# micShield.net
KiCad netlist of a schematic drawn in EAGLE
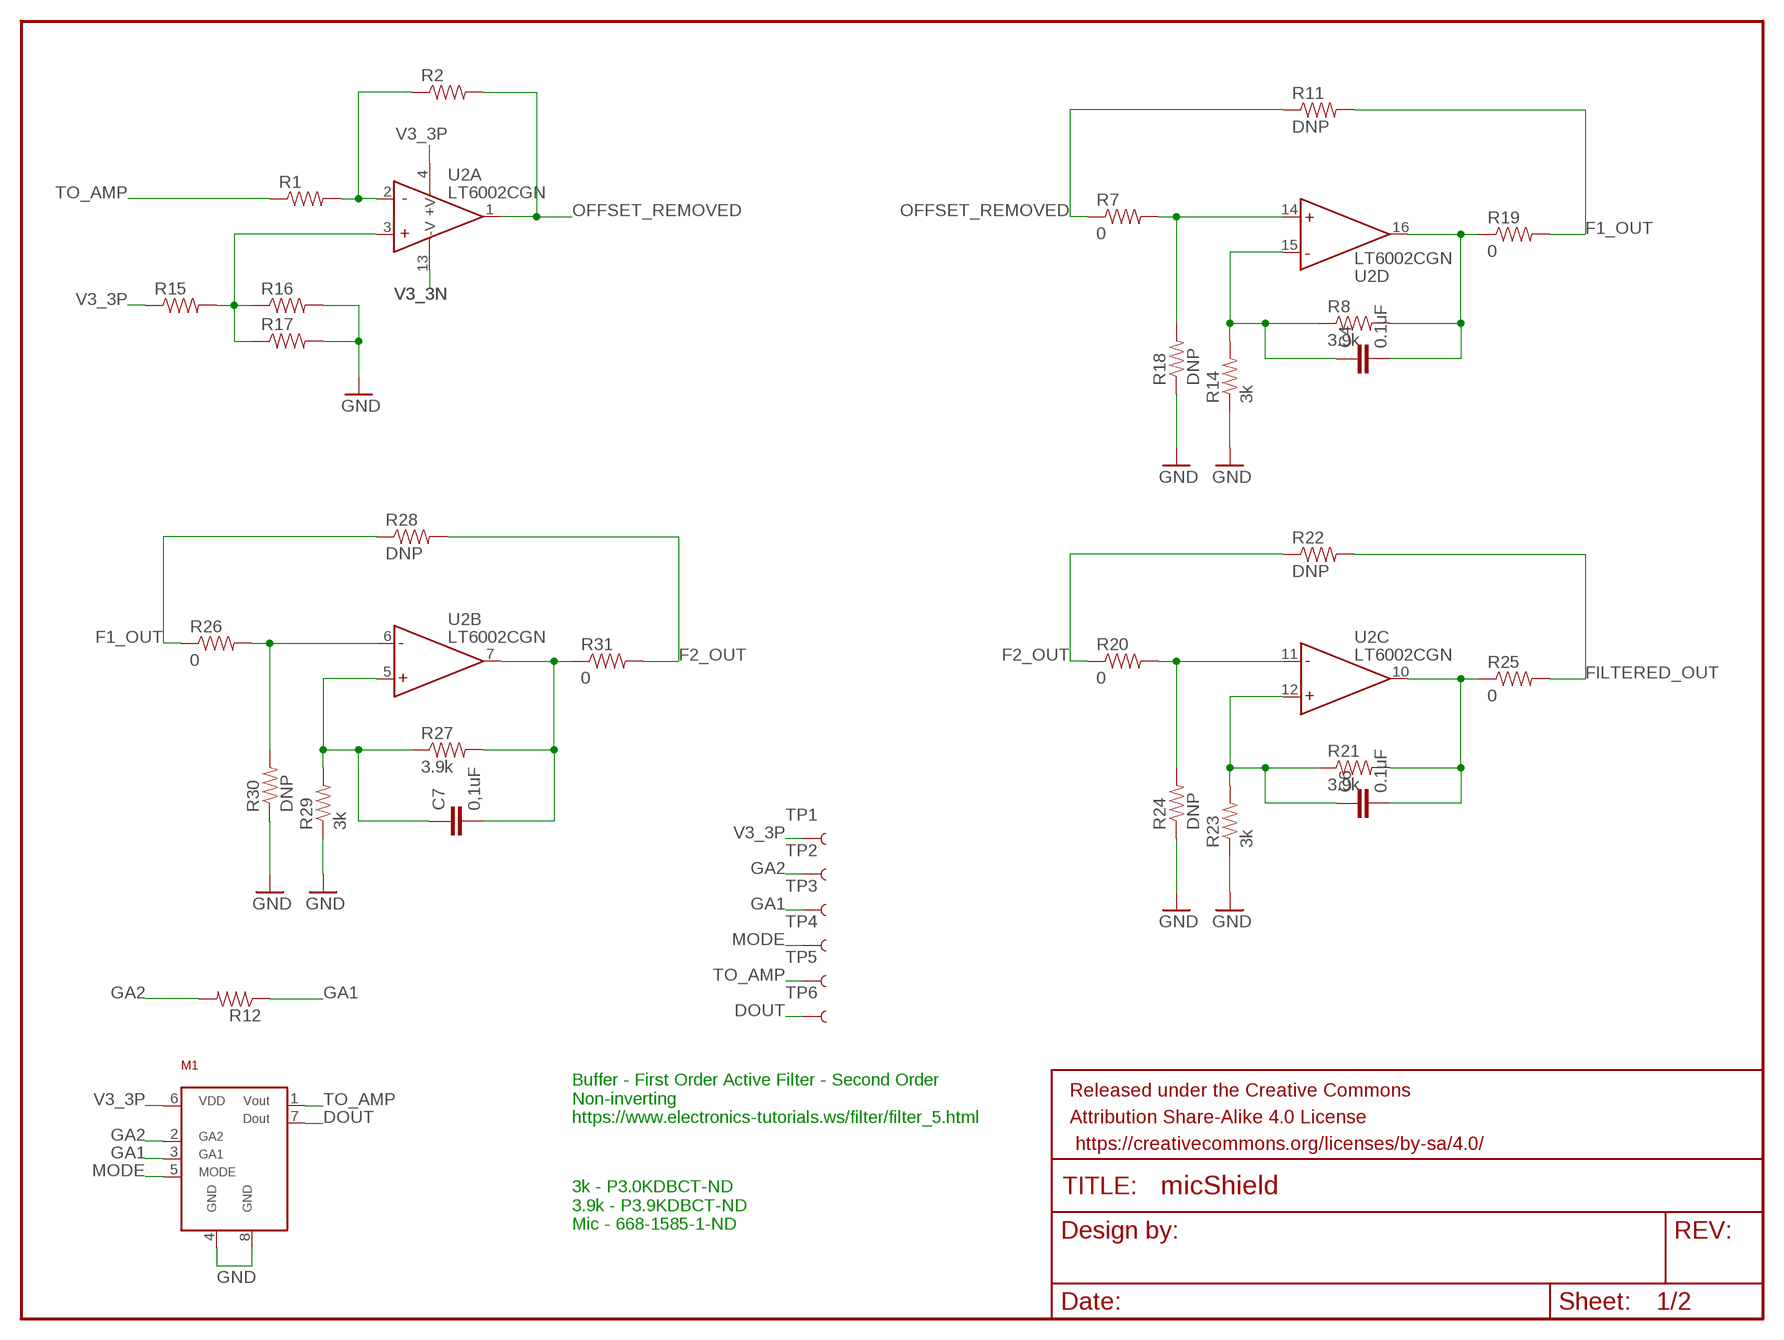
[diagram p0: schematic, sheet 1]
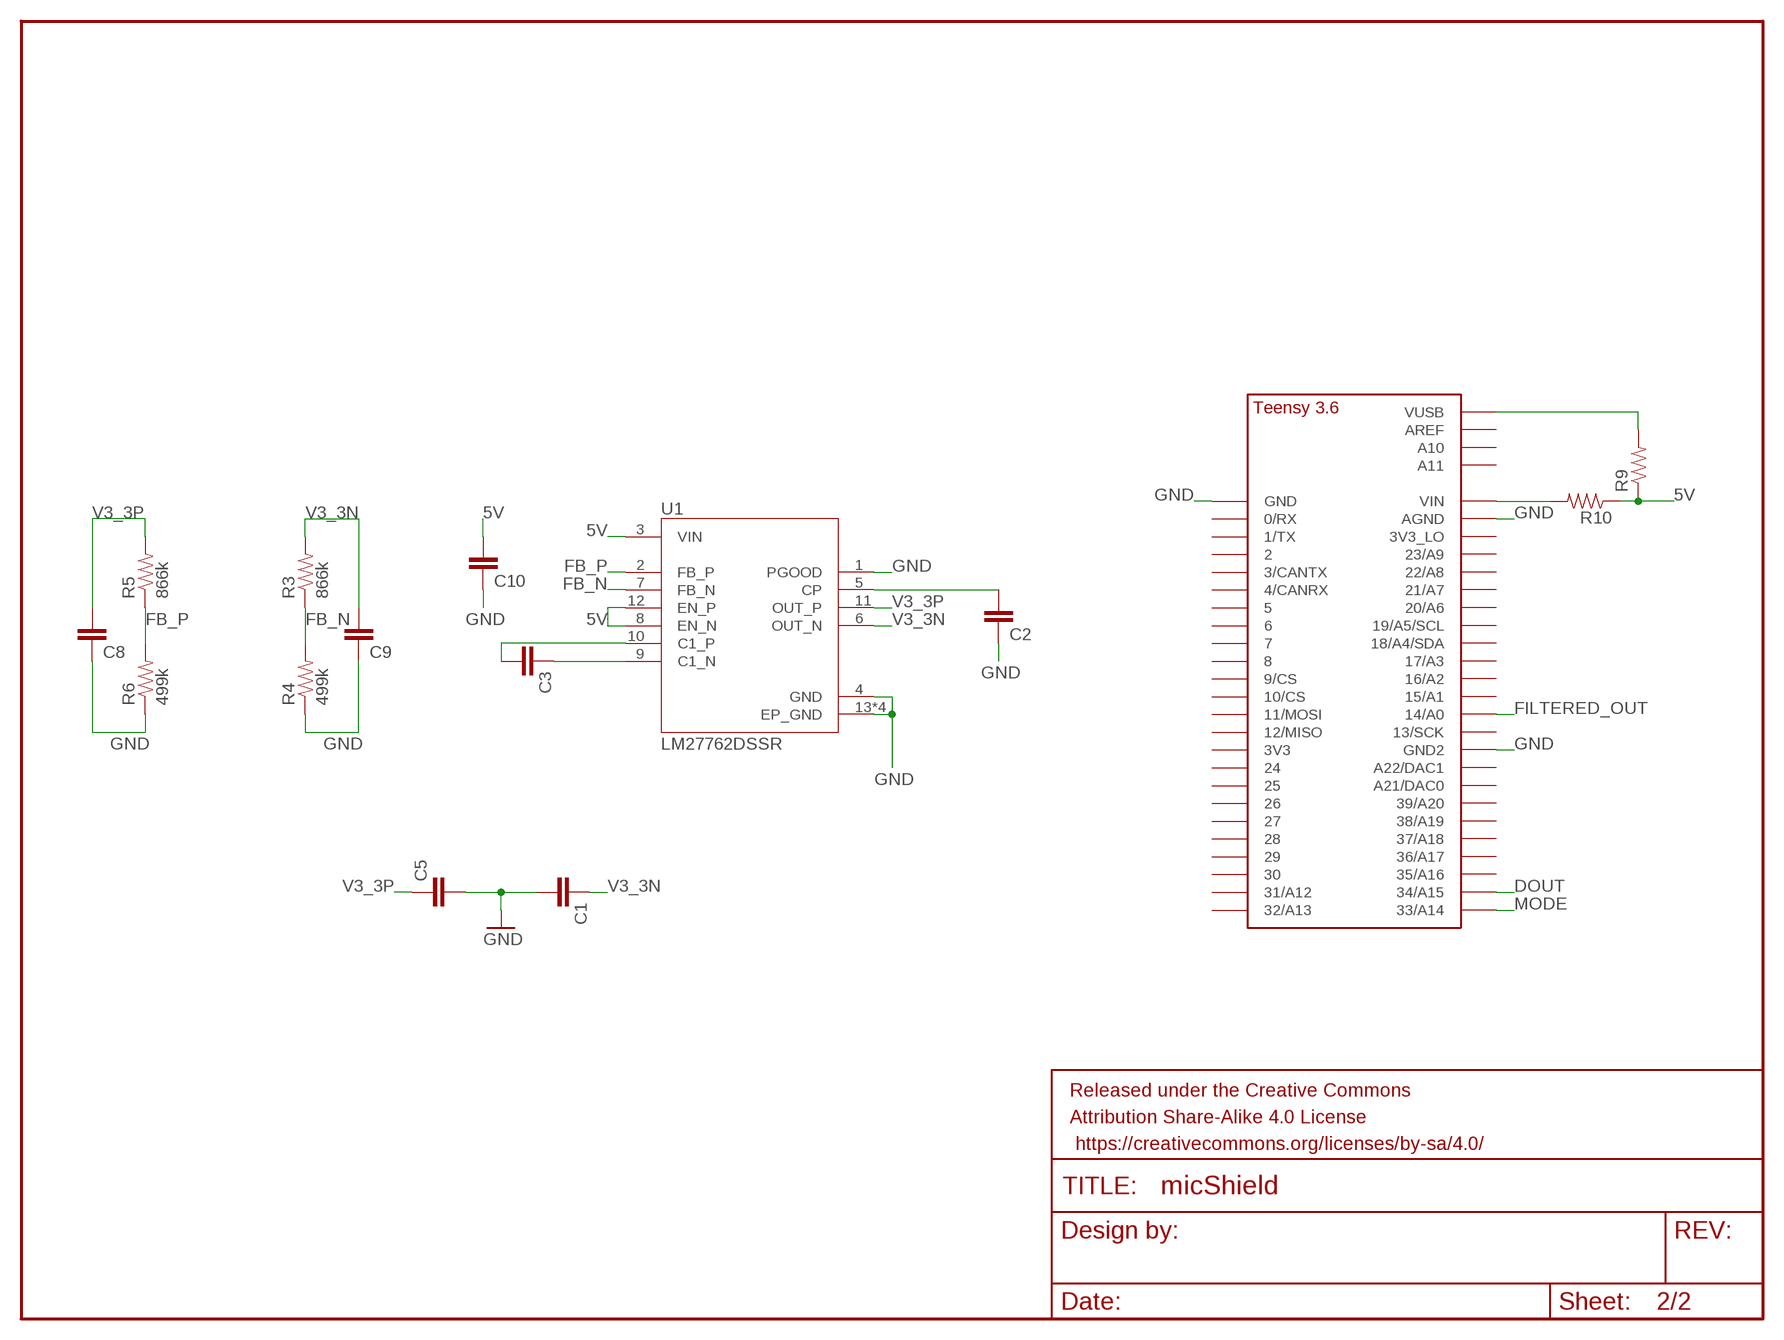
[diagram p1: schematic, sheet 2]

(export (version "E")
  (design (tool "Eeschema 10.0.6"))
  (components
    (comp (ref "C4")
      (value "0.1uF")
      (footprint "eagle-import:0402-CAP")
      (libsource (lib "eagle-import") (part "CAP0402-CAP"))
    )
    (comp (ref "C6")
      (value "0.1uF")
      (footprint "eagle-import:0402-CAP")
      (libsource (lib "eagle-import") (part "CAP0402-CAP"))
    )
    (comp (ref "C7")
      (value "0,1uF")
      (footprint "eagle-import:0402-CAP")
      (libsource (lib "eagle-import") (part "CAP0402-CAP"))
    )
    (comp (ref "FRAME1")
      (value "FRAME-LETTER")
      (footprint "eagle-import:CREATIVE_COMMONS")
      (libsource (lib "eagle-import") (part "FRAME-LETTER"))
    )
    (comp (ref "M1")
      (value "PMM-3738-VM1010-R")
      (footprint "eagle-import:PMM-3738-VM1010-R")
      (libsource (lib "eagle-import") (part "PMM-3738-VM1010-R"))
    )
    (comp (ref "R1")
      (value "RESISTOR0402")
      (footprint "eagle-import:0402-RES")
      (libsource (lib "eagle-import") (part "RESISTOR0402"))
    )
    (comp (ref "R2")
      (value "RESISTOR0402")
      (footprint "eagle-import:0402-RES")
      (libsource (lib "eagle-import") (part "RESISTOR0402"))
    )
    (comp (ref "R7")
      (value "0")
      (footprint "eagle-import:0402-RES")
      (libsource (lib "eagle-import") (part "RESISTOR0402"))
    )
    (comp (ref "R8")
      (value "3.9k")
      (footprint "eagle-import:0402-RES")
      (libsource (lib "eagle-import") (part "RESISTOR0402"))
    )
    (comp (ref "R11")
      (value "DNP")
      (footprint "eagle-import:0402-RES")
      (libsource (lib "eagle-import") (part "RESISTOR0402"))
    )
    (comp (ref "R12")
      (value "RESISTOR0402")
      (footprint "eagle-import:0402-RES")
      (libsource (lib "eagle-import") (part "RESISTOR0402"))
    )
    (comp (ref "R14")
      (value "3k")
      (footprint "eagle-import:0402-RES")
      (libsource (lib "eagle-import") (part "RESISTOR0402"))
    )
    (comp (ref "R15")
      (value "RESISTOR0402")
      (footprint "eagle-import:0402-RES")
      (libsource (lib "eagle-import") (part "RESISTOR0402"))
    )
    (comp (ref "R16")
      (value "RESISTOR0402")
      (footprint "eagle-import:0402-RES")
      (libsource (lib "eagle-import") (part "RESISTOR0402"))
    )
    (comp (ref "R17")
      (value "RESISTOR0402")
      (footprint "eagle-import:0402-RES")
      (libsource (lib "eagle-import") (part "RESISTOR0402"))
    )
    (comp (ref "R18")
      (value "DNP")
      (footprint "eagle-import:0402-RES")
      (libsource (lib "eagle-import") (part "RESISTOR0402"))
    )
    (comp (ref "R19")
      (value "0")
      (footprint "eagle-import:0402-RES")
      (libsource (lib "eagle-import") (part "RESISTOR0402"))
    )
    (comp (ref "R20")
      (value "0")
      (footprint "eagle-import:0402-RES")
      (libsource (lib "eagle-import") (part "RESISTOR0402"))
    )
    (comp (ref "R21")
      (value "3.9k")
      (footprint "eagle-import:0402-RES")
      (libsource (lib "eagle-import") (part "RESISTOR0402"))
    )
    (comp (ref "R22")
      (value "DNP")
      (footprint "eagle-import:0402-RES")
      (libsource (lib "eagle-import") (part "RESISTOR0402"))
    )
    (comp (ref "R23")
      (value "3k")
      (footprint "eagle-import:0402-RES")
      (libsource (lib "eagle-import") (part "RESISTOR0402"))
    )
    (comp (ref "R24")
      (value "DNP")
      (footprint "eagle-import:0402-RES")
      (libsource (lib "eagle-import") (part "RESISTOR0402"))
    )
    (comp (ref "R25")
      (value "0")
      (footprint "eagle-import:0402-RES")
      (libsource (lib "eagle-import") (part "RESISTOR0402"))
    )
    (comp (ref "R26")
      (value "0")
      (footprint "eagle-import:0402-RES")
      (libsource (lib "eagle-import") (part "RESISTOR0402"))
    )
    (comp (ref "R27")
      (value "3.9k")
      (footprint "eagle-import:0402-RES")
      (libsource (lib "eagle-import") (part "RESISTOR0402"))
    )
    (comp (ref "R28")
      (value "DNP")
      (footprint "eagle-import:0402-RES")
      (libsource (lib "eagle-import") (part "RESISTOR0402"))
    )
    (comp (ref "R29")
      (value "3k")
      (footprint "eagle-import:0402-RES")
      (libsource (lib "eagle-import") (part "RESISTOR0402"))
    )
    (comp (ref "R30")
      (value "DNP")
      (footprint "eagle-import:0402-RES")
      (libsource (lib "eagle-import") (part "RESISTOR0402"))
    )
    (comp (ref "R31")
      (value "0")
      (footprint "eagle-import:0402-RES")
      (libsource (lib "eagle-import") (part "RESISTOR0402"))
    )
    (comp (ref "TP1")
      (value "TEST-POINT3")
      (footprint "eagle-import:PAD.03X.03")
      (libsource (lib "eagle-import") (part "TEST-POINT3"))
    )
    (comp (ref "TP2")
      (value "TEST-POINT3")
      (footprint "eagle-import:PAD.03X.03")
      (libsource (lib "eagle-import") (part "TEST-POINT3"))
    )
    (comp (ref "TP3")
      (value "TEST-POINT3")
      (footprint "eagle-import:PAD.03X.03")
      (libsource (lib "eagle-import") (part "TEST-POINT3"))
    )
    (comp (ref "TP4")
      (value "TEST-POINT3")
      (footprint "eagle-import:PAD.03X.03")
      (libsource (lib "eagle-import") (part "TEST-POINT3"))
    )
    (comp (ref "TP5")
      (value "TEST-POINT3")
      (footprint "eagle-import:PAD.03X.03")
      (libsource (lib "eagle-import") (part "TEST-POINT3"))
    )
    (comp (ref "TP6")
      (value "TEST-POINT3")
      (footprint "eagle-import:PAD.03X.03")
      (libsource (lib "eagle-import") (part "TEST-POINT3"))
    )
    (comp (ref "U2")
      (value "LT6002CGN")
      (footprint "eagle-import:SSOP-16_GN")
      (fields (field (name "MANUFACTURER_PART_NUMBER") "LT6002CGN#PBF"))
      (libsource (lib "eagle-import") (part "LT6002CGN"))
    )
    (comp (ref "C1")
      (value "CAP0603-CAP")
      (footprint "eagle-import:0603-CAP")
      (libsource (lib "eagle-import") (part "CAP0603-CAP"))
    )
    (comp (ref "C2")
      (value "CAP0603-CAP")
      (footprint "eagle-import:0603-CAP")
      (libsource (lib "eagle-import") (part "CAP0603-CAP"))
    )
    (comp (ref "C3")
      (value "CAP0402-CAP")
      (footprint "eagle-import:0402-CAP")
      (libsource (lib "eagle-import") (part "CAP0402-CAP"))
    )
    (comp (ref "C5")
      (value "CAP0603-CAP")
      (footprint "eagle-import:0603-CAP")
      (libsource (lib "eagle-import") (part "CAP0603-CAP"))
    )
    (comp (ref "C8")
      (value "CAP0603-CAP")
      (footprint "eagle-import:0603-CAP")
      (libsource (lib "eagle-import") (part "CAP0603-CAP"))
    )
    (comp (ref "C9")
      (value "CAP0603-CAP")
      (footprint "eagle-import:0603-CAP")
      (libsource (lib "eagle-import") (part "CAP0603-CAP"))
    )
    (comp (ref "C10")
      (value "CAP0603-CAP")
      (footprint "eagle-import:0603-CAP")
      (libsource (lib "eagle-import") (part "CAP0603-CAP"))
    )
    (comp (ref "FRAME2")
      (value "FRAME-LETTER")
      (footprint "eagle-import:CREATIVE_COMMONS")
      (libsource (lib "eagle-import") (part "FRAME-LETTER"))
    )
    (comp (ref "R3")
      (value "866k")
      (footprint "eagle-import:0402-RES")
      (libsource (lib "eagle-import") (part "RESISTOR0402"))
    )
    (comp (ref "R4")
      (value "499k")
      (footprint "eagle-import:0402-RES")
      (libsource (lib "eagle-import") (part "RESISTOR0402"))
    )
    (comp (ref "R5")
      (value "866k")
      (footprint "eagle-import:0402-RES")
      (libsource (lib "eagle-import") (part "RESISTOR0402"))
    )
    (comp (ref "R6")
      (value "499k")
      (footprint "eagle-import:0402-RES")
      (libsource (lib "eagle-import") (part "RESISTOR0402"))
    )
    (comp (ref "R9")
      (value "RESISTOR0402")
      (footprint "eagle-import:0402-RES")
      (libsource (lib "eagle-import") (part "RESISTOR0402"))
    )
    (comp (ref "R10")
      (value "RESISTOR0402")
      (footprint "eagle-import:0402-RES")
      (libsource (lib "eagle-import") (part "RESISTOR0402"))
    )
    (comp (ref "U$1")
      (value "TEENSY_3.5/3.6_BASIC")
      (footprint "eagle-import:TEENSY_3.5_3.6_BASIC")
      (libsource (lib "eagle-import") (part "TEENSY_3.5/3.6_BASIC"))
    )
    (comp (ref "U1")
      (value "LM27762DSSR")
      (footprint "eagle-import:VREG_LM27762DSSR")
      (fields (field (name "MF") "Texas Instruments"))
      (libsource (lib "eagle-import") (part "LM27762DSSR"))
    )
  )
  (nets
    (net (code "1") (name "5V") (class "Default")
      (node (ref "C10") (pin "2") (pinfunction "2_2") (pintype "passive"))
      (node (ref "R10") (pin "1") (pinfunction "1_1") (pintype "passive"))
      (node (ref "R9") (pin "1") (pinfunction "1_1") (pintype "passive"))
      (node (ref "U1") (pin "12") (pinfunction "EN_P_12") (pintype "input"))
      (node (ref "U1") (pin "3") (pinfunction "VIN_3") (pintype "input"))
      (node (ref "U1") (pin "8") (pinfunction "EN_N_8") (pintype "input"))
    )
    (net (code "2") (name "DOUT") (class "Default")
      (node (ref "M1") (pin "7") (pinfunction "P$7_7") (pintype "bidirectional"))
      (node (ref "TP6") (pin "P$1") (pinfunction "1_P$1") (pintype "bidirectional"))
      (node (ref "U$1") (pin "34/A15") (pinfunction "34/A15_34/A15") (pintype "bidirectional"))
    )
    (net (code "3") (name "F1_OUT") (class "Default")
      (node (ref "R11") (pin "2") (pinfunction "2_2") (pintype "passive"))
      (node (ref "R19") (pin "2") (pinfunction "2_2") (pintype "passive"))
      (node (ref "R26") (pin "1") (pinfunction "1_1") (pintype "passive"))
      (node (ref "R28") (pin "1") (pinfunction "1_1") (pintype "passive"))
    )
    (net (code "4") (name "F2_OUT") (class "Default")
      (node (ref "R20") (pin "1") (pinfunction "1_1") (pintype "passive"))
      (node (ref "R22") (pin "1") (pinfunction "1_1") (pintype "passive"))
      (node (ref "R28") (pin "2") (pinfunction "2_2") (pintype "passive"))
      (node (ref "R31") (pin "2") (pinfunction "2_2") (pintype "passive"))
    )
    (net (code "5") (name "FB_N") (class "Default")
      (node (ref "R3") (pin "1") (pinfunction "1_1") (pintype "passive"))
      (node (ref "R4") (pin "2") (pinfunction "2_2") (pintype "passive"))
      (node (ref "U1") (pin "7") (pinfunction "FB_N_7") (pintype "input"))
    )
    (net (code "6") (name "FB_P") (class "Default")
      (node (ref "R5") (pin "1") (pinfunction "1_1") (pintype "passive"))
      (node (ref "R6") (pin "2") (pinfunction "2_2") (pintype "passive"))
      (node (ref "U1") (pin "2") (pinfunction "FB_P_2") (pintype "input"))
    )
    (net (code "7") (name "FILTERED_OUT") (class "Default")
      (node (ref "R22") (pin "2") (pinfunction "2_2") (pintype "passive"))
      (node (ref "R25") (pin "2") (pinfunction "2_2") (pintype "passive"))
      (node (ref "U$1") (pin "14/A0") (pinfunction "14/A0_14/A0") (pintype "bidirectional"))
    )
    (net (code "8") (name "GA1") (class "Default")
      (node (ref "M1") (pin "3") (pinfunction "P$3_3") (pintype "bidirectional"))
      (node (ref "R12") (pin "1") (pinfunction "1_1") (pintype "passive"))
      (node (ref "TP3") (pin "P$1") (pinfunction "1_P$1") (pintype "bidirectional"))
    )
    (net (code "9") (name "GA2") (class "Default")
      (node (ref "M1") (pin "2") (pinfunction "P$2_2") (pintype "bidirectional"))
      (node (ref "R12") (pin "2") (pinfunction "2_2") (pintype "passive"))
      (node (ref "TP2") (pin "P$1") (pinfunction "1_P$1") (pintype "bidirectional"))
    )
    (net (code "10") (name "GND") (class "Default")
      (node (ref "C1") (pin "2") (pinfunction "2_2") (pintype "passive"))
      (node (ref "C10") (pin "1") (pinfunction "1_1") (pintype "passive"))
      (node (ref "C2") (pin "1") (pinfunction "1_1") (pintype "passive"))
      (node (ref "C5") (pin "2") (pinfunction "2_2") (pintype "passive"))
      (node (ref "C8") (pin "1") (pinfunction "1_1") (pintype "passive"))
      (node (ref "C9") (pin "1") (pinfunction "1_1") (pintype "passive"))
      (node (ref "M1") (pin "4") (pinfunction "P$4_4") (pintype "bidirectional"))
      (node (ref "M1") (pin "8") (pinfunction "P$8_8") (pintype "bidirectional"))
      (node (ref "R14") (pin "1") (pinfunction "1_1") (pintype "passive"))
      (node (ref "R16") (pin "2") (pinfunction "2_2") (pintype "passive"))
      (node (ref "R17") (pin "2") (pinfunction "2_2") (pintype "passive"))
      (node (ref "R18") (pin "1") (pinfunction "1_1") (pintype "passive"))
      (node (ref "R23") (pin "1") (pinfunction "1_1") (pintype "passive"))
      (node (ref "R24") (pin "1") (pinfunction "1_1") (pintype "passive"))
      (node (ref "R29") (pin "1") (pinfunction "1_1") (pintype "passive"))
      (node (ref "R30") (pin "1") (pinfunction "1_1") (pintype "passive"))
      (node (ref "R4") (pin "1") (pinfunction "1_1") (pintype "passive"))
      (node (ref "R6") (pin "1") (pinfunction "1_1") (pintype "passive"))
      (node (ref "U$1") (pin "AGND") (pinfunction "AGND_AGND") (pintype "bidirectional"))
      (node (ref "U$1") (pin "GND") (pinfunction "GND_GND") (pintype "bidirectional"))
      (node (ref "U$1") (pin "GND2") (pinfunction "GND2_GND2") (pintype "bidirectional"))
      (node (ref "U1") (pin "1") (pinfunction "PGOOD_1") (pintype "output"))
      (node (ref "U1") (pin "13") (pinfunction "EP_GND_13") (pintype "power_in"))
      (node (ref "U1") (pin "13.1") (pinfunction "EP_GND_13.1") (pintype "power_in"))
      (node (ref "U1") (pin "13.2") (pinfunction "EP_GND_13.2") (pintype "power_in"))
      (node (ref "U1") (pin "13.3") (pinfunction "EP_GND_13.3") (pintype "power_in"))
      (node (ref "U1") (pin "4") (pinfunction "GND_4") (pintype "power_in"))
    )
    (net (code "11") (name "MODE") (class "Default")
      (node (ref "M1") (pin "5") (pinfunction "P$5_5") (pintype "bidirectional"))
      (node (ref "TP4") (pin "P$1") (pinfunction "1_P$1") (pintype "bidirectional"))
      (node (ref "U$1") (pin "33/A14") (pinfunction "33/A14_33/A14") (pintype "bidirectional"))
    )
    (net (code "12") (name "Net-(R9-Pad2)") (class "Default")
      (node (ref "R9") (pin "2") (pinfunction "2_2") (pintype "passive"))
      (node (ref "U$1") (pin "VUSB") (pinfunction "VUSB_VUSB") (pintype "bidirectional"))
    )
    (net (code "13") (name "Net-(R10-Pad2)") (class "Default")
      (node (ref "R10") (pin "2") (pinfunction "2_2") (pintype "passive"))
      (node (ref "U$1") (pin "VIN") (pinfunction "VIN_VIN") (pintype "bidirectional"))
    )
    (net (code "14") (name "Net-(U1-C1_N)") (class "Default")
      (node (ref "C3") (pin "1") (pinfunction "1_1") (pintype "passive"))
      (node (ref "U1") (pin "9") (pinfunction "C1_N_9") (pintype "input"))
    )
    (net (code "15") (name "Net-(U1-C1_P)") (class "Default")
      (node (ref "C3") (pin "2") (pinfunction "2_2") (pintype "passive"))
      (node (ref "U1") (pin "10") (pinfunction "C1_P_10") (pintype "input"))
    )
    (net (code "16") (name "Net-(U1-CP)") (class "Default")
      (node (ref "C2") (pin "2") (pinfunction "2_2") (pintype "passive"))
      (node (ref "U1") (pin "5") (pinfunction "CP_5") (pintype "output"))
    )
    (net (code "17") (name "Net-(U2A-+IN)") (class "Default")
      (node (ref "R15") (pin "2") (pinfunction "2_2") (pintype "passive"))
      (node (ref "R16") (pin "1") (pinfunction "1_1") (pintype "passive"))
      (node (ref "R17") (pin "1") (pinfunction "1_1") (pintype "passive"))
      (node (ref "U2") (pin "3") (pinfunction "+IN_3") (pintype "input"))
    )
    (net (code "18") (name "Net-(U2A--IN)") (class "Default")
      (node (ref "R1") (pin "2") (pinfunction "2_2") (pintype "passive"))
      (node (ref "R2") (pin "1") (pinfunction "1_1") (pintype "passive"))
      (node (ref "U2") (pin "2") (pinfunction "-IN_2") (pintype "input"))
    )
    (net (code "19") (name "Net-(U2B-+IN)") (class "Default")
      (node (ref "C7") (pin "1") (pinfunction "1_1") (pintype "passive"))
      (node (ref "R27") (pin "1") (pinfunction "1_1") (pintype "passive"))
      (node (ref "R29") (pin "2") (pinfunction "2_2") (pintype "passive"))
      (node (ref "U2") (pin "5") (pinfunction "+IN_5") (pintype "input"))
    )
    (net (code "20") (name "Net-(U2B--IN)") (class "Default")
      (node (ref "R26") (pin "2") (pinfunction "2_2") (pintype "passive"))
      (node (ref "R30") (pin "2") (pinfunction "2_2") (pintype "passive"))
      (node (ref "U2") (pin "6") (pinfunction "-IN_6") (pintype "input"))
    )
    (net (code "21") (name "Net-(U2B-OUT)") (class "Default")
      (node (ref "C7") (pin "2") (pinfunction "2_2") (pintype "passive"))
      (node (ref "R27") (pin "2") (pinfunction "2_2") (pintype "passive"))
      (node (ref "R31") (pin "1") (pinfunction "1_1") (pintype "passive"))
      (node (ref "U2") (pin "7") (pinfunction "OUT_7") (pintype "output"))
    )
    (net (code "22") (name "Net-(U2C-+IN)") (class "Default")
      (node (ref "C6") (pin "1") (pinfunction "1_1") (pintype "passive"))
      (node (ref "R21") (pin "1") (pinfunction "1_1") (pintype "passive"))
      (node (ref "R23") (pin "2") (pinfunction "2_2") (pintype "passive"))
      (node (ref "U2") (pin "12") (pinfunction "+IN_12") (pintype "input"))
    )
    (net (code "23") (name "Net-(U2C--IN)") (class "Default")
      (node (ref "R20") (pin "2") (pinfunction "2_2") (pintype "passive"))
      (node (ref "R24") (pin "2") (pinfunction "2_2") (pintype "passive"))
      (node (ref "U2") (pin "11") (pinfunction "-IN_11") (pintype "input"))
    )
    (net (code "24") (name "Net-(U2C-OUT)") (class "Default")
      (node (ref "C6") (pin "2") (pinfunction "2_2") (pintype "passive"))
      (node (ref "R21") (pin "2") (pinfunction "2_2") (pintype "passive"))
      (node (ref "R25") (pin "1") (pinfunction "1_1") (pintype "passive"))
      (node (ref "U2") (pin "10") (pinfunction "OUT_10") (pintype "output"))
    )
    (net (code "25") (name "Net-(U2D-+IN)") (class "Default")
      (node (ref "R18") (pin "2") (pinfunction "2_2") (pintype "passive"))
      (node (ref "R7") (pin "2") (pinfunction "2_2") (pintype "passive"))
      (node (ref "U2") (pin "14") (pinfunction "+IN_14") (pintype "input"))
    )
    (net (code "26") (name "Net-(U2D--IN)") (class "Default")
      (node (ref "C4") (pin "1") (pinfunction "1_1") (pintype "passive"))
      (node (ref "R14") (pin "2") (pinfunction "2_2") (pintype "passive"))
      (node (ref "R8") (pin "1") (pinfunction "1_1") (pintype "passive"))
      (node (ref "U2") (pin "15") (pinfunction "-IN_15") (pintype "input"))
    )
    (net (code "27") (name "Net-(U2D-OUT)") (class "Default")
      (node (ref "C4") (pin "2") (pinfunction "2_2") (pintype "passive"))
      (node (ref "R19") (pin "1") (pinfunction "1_1") (pintype "passive"))
      (node (ref "R8") (pin "2") (pinfunction "2_2") (pintype "passive"))
      (node (ref "U2") (pin "16") (pinfunction "OUT_16") (pintype "output"))
    )
    (net (code "28") (name "OFFSET_REMOVED") (class "Default")
      (node (ref "R11") (pin "1") (pinfunction "1_1") (pintype "passive"))
      (node (ref "R2") (pin "2") (pinfunction "2_2") (pintype "passive"))
      (node (ref "R7") (pin "1") (pinfunction "1_1") (pintype "passive"))
      (node (ref "U2") (pin "1") (pinfunction "OUT_1") (pintype "output"))
    )
    (net (code "29") (name "TO_AMP") (class "Default")
      (node (ref "M1") (pin "1") (pinfunction "P$1_1") (pintype "bidirectional"))
      (node (ref "R1") (pin "1") (pinfunction "1_1") (pintype "passive"))
      (node (ref "TP5") (pin "P$1") (pinfunction "1_P$1") (pintype "bidirectional"))
    )
    (net (code "30") (name "V3_3N") (class "Default")
      (node (ref "C1") (pin "1") (pinfunction "1_1") (pintype "passive"))
      (node (ref "C9") (pin "2") (pinfunction "2_2") (pintype "passive"))
      (node (ref "R3") (pin "2") (pinfunction "2_2") (pintype "passive"))
      (node (ref "U1") (pin "6") (pinfunction "OUT_N_6") (pintype "output"))
      (node (ref "U2") (pin "13") (pinfunction "-V_13") (pintype "power_in"))
    )
    (net (code "31") (name "V3_3P") (class "Default")
      (node (ref "C5") (pin "1") (pinfunction "1_1") (pintype "passive"))
      (node (ref "C8") (pin "2") (pinfunction "2_2") (pintype "passive"))
      (node (ref "M1") (pin "6") (pinfunction "P$6_6") (pintype "bidirectional"))
      (node (ref "R15") (pin "1") (pinfunction "1_1") (pintype "passive"))
      (node (ref "R5") (pin "2") (pinfunction "2_2") (pintype "passive"))
      (node (ref "TP1") (pin "P$1") (pinfunction "1_P$1") (pintype "bidirectional"))
      (node (ref "U1") (pin "11") (pinfunction "OUT_P_11") (pintype "output"))
      (node (ref "U2") (pin "4") (pinfunction "+V_4") (pintype "power_in"))
    )
    (net (code "32") (name "unconnected-(U$1-A21{slash}DAC0-Pad21{slash}DAC0)") (class "Default")
      (node (ref "U$1") (pin "21/DAC0") (pinfunction "A21/DAC0_21/DAC0") (pintype "bidirectional"))
    )
    (net (code "33") (name "unconnected-(U$1-Pad0{slash}RX)") (class "Default")
      (node (ref "U$1") (pin "0/RX") (pinfunction "0/RX_0/RX") (pintype "bidirectional"))
    )
    (net (code "34") (name "unconnected-(U$1-Pad1{slash}TX)") (class "Default")
      (node (ref "U$1") (pin "1/TX") (pinfunction "1/TX_1/TX") (pintype "bidirectional"))
    )
    (net (code "35") (name "unconnected-(U$1-Pad2)") (class "Default")
      (node (ref "U$1") (pin "2") (pinfunction "2_2") (pintype "bidirectional"))
    )
    (net (code "36") (name "unconnected-(U$1-Pad3V3)") (class "Default")
      (node (ref "U$1") (pin "3V3") (pinfunction "3V3_3V3") (pintype "bidirectional"))
    )
    (net (code "37") (name "unconnected-(U$1-Pad3V3_LO)") (class "Default")
      (node (ref "U$1") (pin "3V3_LO") (pinfunction "3V3_LO_3V3_LO") (pintype "bidirectional"))
    )
    (net (code "38") (name "unconnected-(U$1-Pad3{slash}CANTX)") (class "Default")
      (node (ref "U$1") (pin "3/CANTX") (pinfunction "3/CANTX_3/CANTX") (pintype "bidirectional"))
    )
    (net (code "39") (name "unconnected-(U$1-Pad4{slash}CANRX)") (class "Default")
      (node (ref "U$1") (pin "4/CANRX") (pinfunction "4/CANRX_4/CANRX") (pintype "bidirectional"))
    )
    (net (code "40") (name "unconnected-(U$1-Pad5)") (class "Default")
      (node (ref "U$1") (pin "5") (pinfunction "5_5") (pintype "bidirectional"))
    )
    (net (code "41") (name "unconnected-(U$1-Pad6)") (class "Default")
      (node (ref "U$1") (pin "6") (pinfunction "6_6") (pintype "bidirectional"))
    )
    (net (code "42") (name "unconnected-(U$1-Pad7)") (class "Default")
      (node (ref "U$1") (pin "7") (pinfunction "7_7") (pintype "bidirectional"))
    )
    (net (code "43") (name "unconnected-(U$1-Pad8)") (class "Default")
      (node (ref "U$1") (pin "8") (pinfunction "8_8") (pintype "bidirectional"))
    )
    (net (code "44") (name "unconnected-(U$1-Pad9{slash}CS)") (class "Default")
      (node (ref "U$1") (pin "9/CS") (pinfunction "9/CS_9/CS") (pintype "bidirectional"))
    )
    (net (code "45") (name "unconnected-(U$1-Pad10{slash}CS)") (class "Default")
      (node (ref "U$1") (pin "10/CS") (pinfunction "10/CS_10/CS") (pintype "bidirectional"))
    )
    (net (code "46") (name "unconnected-(U$1-Pad11{slash}MOSI)") (class "Default")
      (node (ref "U$1") (pin "11/MOSI") (pinfunction "11/MOSI_11/MOSI") (pintype "bidirectional"))
    )
    (net (code "47") (name "unconnected-(U$1-Pad12{slash}MISO)") (class "Default")
      (node (ref "U$1") (pin "12/MISO") (pinfunction "12/MISO_12/MISO") (pintype "bidirectional"))
    )
    (net (code "48") (name "unconnected-(U$1-Pad13{slash}SCK)") (class "Default")
      (node (ref "U$1") (pin "13/SCK") (pinfunction "13/SCK_13/SCK") (pintype "bidirectional"))
    )
    (net (code "49") (name "unconnected-(U$1-Pad15{slash}A1)") (class "Default")
      (node (ref "U$1") (pin "15/A1") (pinfunction "15/A1_15/A1") (pintype "bidirectional"))
    )
    (net (code "50") (name "unconnected-(U$1-Pad16{slash}A2)") (class "Default")
      (node (ref "U$1") (pin "16/A2") (pinfunction "16/A2_16/A2") (pintype "bidirectional"))
    )
    (net (code "51") (name "unconnected-(U$1-Pad17{slash}A3)") (class "Default")
      (node (ref "U$1") (pin "17/A3") (pinfunction "17/A3_17/A3") (pintype "bidirectional"))
    )
    (net (code "52") (name "unconnected-(U$1-Pad18{slash}A4{slash}SDA)") (class "Default")
      (node (ref "U$1") (pin "18/A4/SDA") (pinfunction "18/A4/SDA_18/A4/SDA") (pintype "bidirectional"))
    )
    (net (code "53") (name "unconnected-(U$1-Pad19{slash}A5{slash}SCL)") (class "Default")
      (node (ref "U$1") (pin "19/A5/SCL") (pinfunction "19/A5/SCL_19/A5/SCL") (pintype "bidirectional"))
    )
    (net (code "54") (name "unconnected-(U$1-Pad20{slash}A6)") (class "Default")
      (node (ref "U$1") (pin "20/A6") (pinfunction "20/A6_20/A6") (pintype "bidirectional"))
    )
    (net (code "55") (name "unconnected-(U$1-Pad21{slash}A7)") (class "Default")
      (node (ref "U$1") (pin "21/A7") (pinfunction "21/A7_21/A7") (pintype "bidirectional"))
    )
    (net (code "56") (name "unconnected-(U$1-Pad22{slash}A8)") (class "Default")
      (node (ref "U$1") (pin "22/A8") (pinfunction "22/A8_22/A8") (pintype "bidirectional"))
    )
    (net (code "57") (name "unconnected-(U$1-Pad23{slash}A9)") (class "Default")
      (node (ref "U$1") (pin "23/A9") (pinfunction "23/A9_23/A9") (pintype "bidirectional"))
    )
    (net (code "58") (name "unconnected-(U$1-Pad24)") (class "Default")
      (node (ref "U$1") (pin "24") (pinfunction "24_24") (pintype "bidirectional"))
    )
    (net (code "59") (name "unconnected-(U$1-Pad25)") (class "Default")
      (node (ref "U$1") (pin "25") (pinfunction "25_25") (pintype "bidirectional"))
    )
    (net (code "60") (name "unconnected-(U$1-Pad26)") (class "Default")
      (node (ref "U$1") (pin "26") (pinfunction "26_26") (pintype "bidirectional"))
    )
    (net (code "61") (name "unconnected-(U$1-Pad27)") (class "Default")
      (node (ref "U$1") (pin "27") (pinfunction "27_27") (pintype "bidirectional"))
    )
    (net (code "62") (name "unconnected-(U$1-Pad28)") (class "Default")
      (node (ref "U$1") (pin "28") (pinfunction "28_28") (pintype "bidirectional"))
    )
    (net (code "63") (name "unconnected-(U$1-Pad29)") (class "Default")
      (node (ref "U$1") (pin "29") (pinfunction "29_29") (pintype "bidirectional"))
    )
    (net (code "64") (name "unconnected-(U$1-Pad30)") (class "Default")
      (node (ref "U$1") (pin "30") (pinfunction "30_30") (pintype "bidirectional"))
    )
    (net (code "65") (name "unconnected-(U$1-Pad31{slash}A12)") (class "Default")
      (node (ref "U$1") (pin "31/A12") (pinfunction "31/A12_31/A12") (pintype "bidirectional"))
    )
    (net (code "66") (name "unconnected-(U$1-Pad32{slash}A13)") (class "Default")
      (node (ref "U$1") (pin "32/A13") (pinfunction "32/A13_32/A13") (pintype "bidirectional"))
    )
    (net (code "67") (name "unconnected-(U$1-Pad35{slash}A16)") (class "Default")
      (node (ref "U$1") (pin "35/A16") (pinfunction "35/A16_35/A16") (pintype "bidirectional"))
    )
    (net (code "68") (name "unconnected-(U$1-Pad36{slash}A17)") (class "Default")
      (node (ref "U$1") (pin "36/A17") (pinfunction "36/A17_36/A17") (pintype "bidirectional"))
    )
    (net (code "69") (name "unconnected-(U$1-Pad37{slash}A18)") (class "Default")
      (node (ref "U$1") (pin "37/A18") (pinfunction "37/A18_37/A18") (pintype "bidirectional"))
    )
    (net (code "70") (name "unconnected-(U$1-Pad38{slash}A19)") (class "Default")
      (node (ref "U$1") (pin "38/A19") (pinfunction "38/A19_38/A19") (pintype "bidirectional"))
    )
    (net (code "71") (name "unconnected-(U$1-Pad39{slash}A20)") (class "Default")
      (node (ref "U$1") (pin "39/A20") (pinfunction "39/A20_39/A20") (pintype "bidirectional"))
    )
    (net (code "72") (name "unconnected-(U$1-PadA10)") (class "Default")
      (node (ref "U$1") (pin "A10") (pinfunction "A10_A10") (pintype "bidirectional"))
    )
    (net (code "73") (name "unconnected-(U$1-PadA11)") (class "Default")
      (node (ref "U$1") (pin "A11") (pinfunction "A11_A11") (pintype "bidirectional"))
    )
    (net (code "74") (name "unconnected-(U$1-PadA22{slash}DAC1)") (class "Default")
      (node (ref "U$1") (pin "A22/DAC1") (pinfunction "A22/DAC1_A22/DAC1") (pintype "bidirectional"))
    )
    (net (code "75") (name "unconnected-(U$1-PadAREF)") (class "Default")
      (node (ref "U$1") (pin "AREF") (pinfunction "AREF_AREF") (pintype "bidirectional"))
    )
  )
)
